# SDRAM.net
KiCad netlist of a schematic drawn in Altium Designer
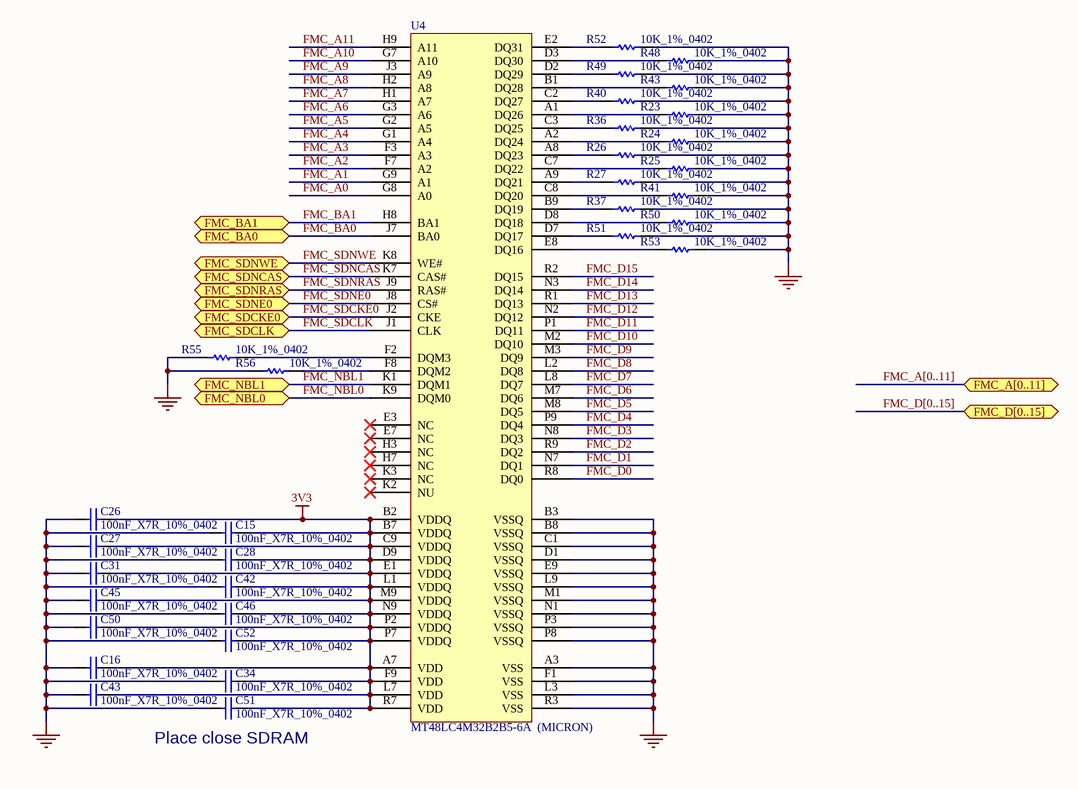
[diagram p0: SDRAM.SchDoc]

(export (version "E")
  (design (tool "Eeschema 10.0.6"))
  (components
    (comp (ref "C15")
      (value "100nF_X7R_10%_0402")
      (footprint "0402C")
      (description "Capacitor,100nF,16V,X7R,10%,0402,YAGEO")
      (libsource (lib "MCD_TOOLS") (part "Cap_100nF_X7R_10%_0402"))
    )
    (comp (ref "C16")
      (value "100nF_X7R_10%_0402")
      (footprint "0402C")
      (description "Capacitor,100nF,16V,X7R,10%,0402,YAGEO")
      (libsource (lib "MCD_TOOLS") (part "Cap_100nF_X7R_10%_0402"))
    )
    (comp (ref "C26")
      (value "100nF_X7R_10%_0402")
      (footprint "0402C")
      (description "Capacitor,100nF,16V,X7R,10%,0402,YAGEO")
      (libsource (lib "MCD_TOOLS") (part "Cap_100nF_X7R_10%_0402"))
    )
    (comp (ref "C27")
      (value "100nF_X7R_10%_0402")
      (footprint "0402C")
      (description "Capacitor,100nF,16V,X7R,10%,0402,YAGEO")
      (libsource (lib "MCD_TOOLS") (part "Cap_100nF_X7R_10%_0402"))
    )
    (comp (ref "C28")
      (value "100nF_X7R_10%_0402")
      (footprint "0402C")
      (description "Capacitor,100nF,16V,X7R,10%,0402,YAGEO")
      (libsource (lib "MCD_TOOLS") (part "Cap_100nF_X7R_10%_0402"))
    )
    (comp (ref "C31")
      (value "100nF_X7R_10%_0402")
      (footprint "0402C")
      (description "Capacitor,100nF,16V,X7R,10%,0402,YAGEO")
      (libsource (lib "MCD_TOOLS") (part "Cap_100nF_X7R_10%_0402"))
    )
    (comp (ref "C34")
      (value "100nF_X7R_10%_0402")
      (footprint "0402C")
      (description "Capacitor,100nF,16V,X7R,10%,0402,YAGEO")
      (libsource (lib "MCD_TOOLS") (part "Cap_100nF_X7R_10%_0402"))
    )
    (comp (ref "C42")
      (value "100nF_X7R_10%_0402")
      (footprint "0402C")
      (description "Capacitor,100nF,16V,X7R,10%,0402,YAGEO")
      (libsource (lib "MCD_TOOLS") (part "Cap_100nF_X7R_10%_0402"))
    )
    (comp (ref "C43")
      (value "100nF_X7R_10%_0402")
      (footprint "0402C")
      (description "Capacitor,100nF,16V,X7R,10%,0402,YAGEO")
      (libsource (lib "MCD_TOOLS") (part "Cap_100nF_X7R_10%_0402"))
    )
    (comp (ref "C45")
      (value "100nF_X7R_10%_0402")
      (footprint "0402C")
      (description "Capacitor,100nF,16V,X7R,10%,0402,YAGEO")
      (libsource (lib "MCD_TOOLS") (part "Cap_100nF_X7R_10%_0402"))
    )
    (comp (ref "C46")
      (value "100nF_X7R_10%_0402")
      (footprint "0402C")
      (description "Capacitor,100nF,16V,X7R,10%,0402,YAGEO")
      (libsource (lib "MCD_TOOLS") (part "Cap_100nF_X7R_10%_0402"))
    )
    (comp (ref "C50")
      (value "100nF_X7R_10%_0402")
      (footprint "0402C")
      (description "Capacitor,100nF,16V,X7R,10%,0402,YAGEO")
      (libsource (lib "MCD_TOOLS") (part "Cap_100nF_X7R_10%_0402"))
    )
    (comp (ref "C51")
      (value "100nF_X7R_10%_0402")
      (footprint "0402C")
      (description "Capacitor,100nF,16V,X7R,10%,0402,YAGEO")
      (libsource (lib "MCD_TOOLS") (part "Cap_100nF_X7R_10%_0402"))
    )
    (comp (ref "C52")
      (value "100nF_X7R_10%_0402")
      (footprint "0402C")
      (description "Capacitor,100nF,16V,X7R,10%,0402,YAGEO")
      (libsource (lib "MCD_TOOLS") (part "Cap_100nF_X7R_10%_0402"))
    )
    (comp (ref "R23")
      (value "10K_1%_0402")
      (footprint "0402R")
      (description "Resistor,10K,0402,1%,YAGEO")
      (libsource (lib "MCD_TOOLS") (part "Res_10K_1%_0402"))
    )
    (comp (ref "R24")
      (value "10K_1%_0402")
      (footprint "0402R")
      (description "Resistor,10K,0402,1%,YAGEO")
      (libsource (lib "MCD_TOOLS") (part "Res_10K_1%_0402"))
    )
    (comp (ref "R25")
      (value "10K_1%_0402")
      (footprint "0402R")
      (description "Resistor,10K,0402,1%,YAGEO")
      (libsource (lib "MCD_TOOLS") (part "Res_10K_1%_0402"))
    )
    (comp (ref "R26")
      (value "10K_1%_0402")
      (footprint "0402R")
      (description "Resistor,10K,0402,1%,YAGEO")
      (libsource (lib "MCD_TOOLS") (part "Res_10K_1%_0402"))
    )
    (comp (ref "R27")
      (value "10K_1%_0402")
      (footprint "0402R")
      (description "Resistor,10K,0402,1%,YAGEO")
      (libsource (lib "MCD_TOOLS") (part "Res_10K_1%_0402"))
    )
    (comp (ref "R36")
      (value "10K_1%_0402")
      (footprint "0402R")
      (description "Resistor,10K,0402,1%,YAGEO")
      (libsource (lib "MCD_TOOLS") (part "Res_10K_1%_0402"))
    )
    (comp (ref "R37")
      (value "10K_1%_0402")
      (footprint "0402R")
      (description "Resistor,10K,0402,1%,YAGEO")
      (libsource (lib "MCD_TOOLS") (part "Res_10K_1%_0402"))
    )
    (comp (ref "R40")
      (value "10K_1%_0402")
      (footprint "0402R")
      (description "Resistor,10K,0402,1%,YAGEO")
      (libsource (lib "MCD_TOOLS") (part "Res_10K_1%_0402"))
    )
    (comp (ref "R41")
      (value "10K_1%_0402")
      (footprint "0402R")
      (description "Resistor,10K,0402,1%,YAGEO")
      (libsource (lib "MCD_TOOLS") (part "Res_10K_1%_0402"))
    )
    (comp (ref "R43")
      (value "10K_1%_0402")
      (footprint "0402R")
      (description "Resistor,10K,0402,1%,YAGEO")
      (libsource (lib "MCD_TOOLS") (part "Res_10K_1%_0402"))
    )
    (comp (ref "R48")
      (value "10K_1%_0402")
      (footprint "0402R")
      (description "Resistor,10K,0402,1%,YAGEO")
      (libsource (lib "MCD_TOOLS") (part "Res_10K_1%_0402"))
    )
    (comp (ref "R49")
      (value "10K_1%_0402")
      (footprint "0402R")
      (description "Resistor,10K,0402,1%,YAGEO")
      (libsource (lib "MCD_TOOLS") (part "Res_10K_1%_0402"))
    )
    (comp (ref "R50")
      (value "10K_1%_0402")
      (footprint "0402R")
      (description "Resistor,10K,0402,1%,YAGEO")
      (libsource (lib "MCD_TOOLS") (part "Res_10K_1%_0402"))
    )
    (comp (ref "R51")
      (value "10K_1%_0402")
      (footprint "0402R")
      (description "Resistor,10K,0402,1%,YAGEO")
      (libsource (lib "MCD_TOOLS") (part "Res_10K_1%_0402"))
    )
    (comp (ref "R52")
      (value "10K_1%_0402")
      (footprint "0402R")
      (description "Resistor,10K,0402,1%,YAGEO")
      (libsource (lib "MCD_TOOLS") (part "Res_10K_1%_0402"))
    )
    (comp (ref "R53")
      (value "10K_1%_0402")
      (footprint "0402R")
      (description "Resistor,10K,0402,1%,YAGEO")
      (libsource (lib "MCD_TOOLS") (part "Res_10K_1%_0402"))
    )
    (comp (ref "R55")
      (value "10K_1%_0402")
      (footprint "0402R")
      (description "Resistor,10K,0402,1%,YAGEO")
      (libsource (lib "MCD_TOOLS") (part "Res_10K_1%_0402"))
    )
    (comp (ref "R56")
      (value "10K_1%_0402")
      (footprint "0402R")
      (description "Resistor,10K,0402,1%,YAGEO")
      (libsource (lib "MCD_TOOLS") (part "Res_10K_1%_0402"))
    )
    (comp (ref "U4")
      (value "MT48LC4M32B2B5-6A  (MICRON)")
      (footprint "FBGA90_0R8_8X13")
      (description "SDRAM 128MBIT (4M x 32) 166MHZ 90-VFBGA (8x13)")
      (libsource (lib "MCD_TOOLS") (part "MT48LC4M32B2B5-6A"))
    )
  )
  (nets
    (net (code "1") (name "/FMC_A0") (class "Default")
      (node (ref "U4") (pin "G8") (pinfunction "A0_G8") (pintype "passive"))
    )
    (net (code "2") (name "/FMC_A1") (class "Default")
      (node (ref "U4") (pin "G9") (pinfunction "A1_G9") (pintype "passive"))
    )
    (net (code "3") (name "/FMC_A2") (class "Default")
      (node (ref "U4") (pin "F7") (pinfunction "A2_F7") (pintype "passive"))
    )
    (net (code "4") (name "/FMC_A3") (class "Default")
      (node (ref "U4") (pin "F3") (pinfunction "A3_F3") (pintype "passive"))
    )
    (net (code "5") (name "/FMC_A4") (class "Default")
      (node (ref "U4") (pin "G1") (pinfunction "A4_G1") (pintype "passive"))
    )
    (net (code "6") (name "/FMC_A5") (class "Default")
      (node (ref "U4") (pin "G2") (pinfunction "A5_G2") (pintype "passive"))
    )
    (net (code "7") (name "/FMC_A6") (class "Default")
      (node (ref "U4") (pin "G3") (pinfunction "A6_G3") (pintype "passive"))
    )
    (net (code "8") (name "/FMC_A7") (class "Default")
      (node (ref "U4") (pin "H1") (pinfunction "A7_H1") (pintype "passive"))
    )
    (net (code "9") (name "/FMC_A8") (class "Default")
      (node (ref "U4") (pin "H2") (pinfunction "A8_H2") (pintype "passive"))
    )
    (net (code "10") (name "/FMC_A9") (class "Default")
      (node (ref "U4") (pin "J3") (pinfunction "A9_J3") (pintype "passive"))
    )
    (net (code "11") (name "/FMC_A10") (class "Default")
      (node (ref "U4") (pin "G7") (pinfunction "A10_G7") (pintype "passive"))
    )
    (net (code "12") (name "/FMC_A11") (class "Default")
      (node (ref "U4") (pin "H9") (pinfunction "A11_H9") (pintype "passive"))
    )
    (net (code "14") (name "/FMC_BA0") (class "Default")
      (node (ref "U4") (pin "J7") (pinfunction "BA0_J7") (pintype "passive"))
    )
    (net (code "15") (name "/FMC_BA1") (class "Default")
      (node (ref "U4") (pin "H8") (pinfunction "BA1_H8") (pintype "passive"))
    )
    (net (code "16") (name "/FMC_D0") (class "Default")
      (node (ref "U4") (pin "R8") (pinfunction "DQ0_R8") (pintype "passive"))
    )
    (net (code "17") (name "/FMC_D1") (class "Default")
      (node (ref "U4") (pin "N7") (pinfunction "DQ1_N7") (pintype "passive"))
    )
    (net (code "18") (name "/FMC_D2") (class "Default")
      (node (ref "U4") (pin "R9") (pinfunction "DQ2_R9") (pintype "passive"))
    )
    (net (code "19") (name "/FMC_D3") (class "Default")
      (node (ref "U4") (pin "N8") (pinfunction "DQ3_N8") (pintype "passive"))
    )
    (net (code "20") (name "/FMC_D4") (class "Default")
      (node (ref "U4") (pin "P9") (pinfunction "DQ4_P9") (pintype "passive"))
    )
    (net (code "21") (name "/FMC_D5") (class "Default")
      (node (ref "U4") (pin "M8") (pinfunction "DQ5_M8") (pintype "passive"))
    )
    (net (code "22") (name "/FMC_D6") (class "Default")
      (node (ref "U4") (pin "M7") (pinfunction "DQ6_M7") (pintype "passive"))
    )
    (net (code "23") (name "/FMC_D7") (class "Default")
      (node (ref "U4") (pin "L8") (pinfunction "DQ7_L8") (pintype "passive"))
    )
    (net (code "24") (name "/FMC_D8") (class "Default")
      (node (ref "U4") (pin "L2") (pinfunction "DQ8_L2") (pintype "passive"))
    )
    (net (code "25") (name "/FMC_D9") (class "Default")
      (node (ref "U4") (pin "M3") (pinfunction "DQ9_M3") (pintype "passive"))
    )
    (net (code "26") (name "/FMC_D10") (class "Default")
      (node (ref "U4") (pin "M2") (pinfunction "DQ10_M2") (pintype "passive"))
    )
    (net (code "27") (name "/FMC_D11") (class "Default")
      (node (ref "U4") (pin "P1") (pinfunction "DQ11_P1") (pintype "passive"))
    )
    (net (code "28") (name "/FMC_D12") (class "Default")
      (node (ref "U4") (pin "N2") (pinfunction "DQ12_N2") (pintype "passive"))
    )
    (net (code "29") (name "/FMC_D13") (class "Default")
      (node (ref "U4") (pin "R1") (pinfunction "DQ13_R1") (pintype "passive"))
    )
    (net (code "30") (name "/FMC_D14") (class "Default")
      (node (ref "U4") (pin "N3") (pinfunction "DQ14_N3") (pintype "passive"))
    )
    (net (code "31") (name "/FMC_D15") (class "Default")
      (node (ref "U4") (pin "R2") (pinfunction "DQ15_R2") (pintype "passive"))
    )
    (net (code "33") (name "/FMC_NBL0") (class "Default")
      (node (ref "U4") (pin "K9") (pinfunction "DQM0_K9") (pintype "passive"))
    )
    (net (code "34") (name "/FMC_NBL1") (class "Default")
      (node (ref "U4") (pin "K1") (pinfunction "DQM1_K1") (pintype "passive"))
    )
    (net (code "35") (name "/FMC_SDCKE0") (class "Default")
      (node (ref "U4") (pin "J2") (pinfunction "CKE_J2") (pintype "passive"))
    )
    (net (code "36") (name "/FMC_SDCLK") (class "Default")
      (node (ref "U4") (pin "J1") (pinfunction "CLK_J1") (pintype "passive"))
    )
    (net (code "37") (name "/FMC_SDNCAS") (class "Default")
      (node (ref "U4") (pin "K7") (pinfunction "CAS#_K7") (pintype "passive"))
    )
    (net (code "38") (name "/FMC_SDNE0") (class "Default")
      (node (ref "U4") (pin "J8") (pinfunction "CS#_J8") (pintype "passive"))
    )
    (net (code "39") (name "/FMC_SDNRAS") (class "Default")
      (node (ref "U4") (pin "J9") (pinfunction "RAS#_J9") (pintype "passive"))
    )
    (net (code "40") (name "/FMC_SDNWE") (class "Default")
      (node (ref "U4") (pin "K8") (pinfunction "WE#_K8") (pintype "passive"))
    )
    (net (code "41") (name "3V3") (class "Default")
      (node (ref "C15") (pin "2") (pinfunction "2_2") (pintype "passive"))
      (node (ref "C16") (pin "2") (pinfunction "2_2") (pintype "passive"))
      (node (ref "C26") (pin "2") (pinfunction "2_2") (pintype "passive"))
      (node (ref "C27") (pin "2") (pinfunction "2_2") (pintype "passive"))
      (node (ref "C28") (pin "2") (pinfunction "2_2") (pintype "passive"))
      (node (ref "C31") (pin "2") (pinfunction "2_2") (pintype "passive"))
      (node (ref "C34") (pin "2") (pinfunction "2_2") (pintype "passive"))
      (node (ref "C42") (pin "2") (pinfunction "2_2") (pintype "passive"))
      (node (ref "C43") (pin "2") (pinfunction "2_2") (pintype "passive"))
      (node (ref "C45") (pin "2") (pinfunction "2_2") (pintype "passive"))
      (node (ref "C46") (pin "2") (pinfunction "2_2") (pintype "passive"))
      (node (ref "C50") (pin "2") (pinfunction "2_2") (pintype "passive"))
      (node (ref "C51") (pin "2") (pinfunction "2_2") (pintype "passive"))
      (node (ref "C52") (pin "2") (pinfunction "2_2") (pintype "passive"))
      (node (ref "U4") (pin "A7") (pinfunction "VDD_A7") (pintype "passive"))
      (node (ref "U4") (pin "B2") (pinfunction "VDDQ_B2") (pintype "passive"))
      (node (ref "U4") (pin "B7") (pinfunction "VDDQ_B7") (pintype "passive"))
      (node (ref "U4") (pin "C9") (pinfunction "VDDQ_C9") (pintype "passive"))
      (node (ref "U4") (pin "D9") (pinfunction "VDDQ_D9") (pintype "passive"))
      (node (ref "U4") (pin "E1") (pinfunction "VDDQ_E1") (pintype "passive"))
      (node (ref "U4") (pin "F9") (pinfunction "VDD_F9") (pintype "passive"))
      (node (ref "U4") (pin "L1") (pinfunction "VDDQ_L1") (pintype "passive"))
      (node (ref "U4") (pin "L7") (pinfunction "VDD_L7") (pintype "passive"))
      (node (ref "U4") (pin "M9") (pinfunction "VDDQ_M9") (pintype "passive"))
      (node (ref "U4") (pin "N9") (pinfunction "VDDQ_N9") (pintype "passive"))
      (node (ref "U4") (pin "P2") (pinfunction "VDDQ_P2") (pintype "passive"))
      (node (ref "U4") (pin "P7") (pinfunction "VDDQ_P7") (pintype "passive"))
      (node (ref "U4") (pin "R7") (pinfunction "VDD_R7") (pintype "passive"))
    )
    (net (code "42") (name "GND") (class "Default")
      (node (ref "C15") (pin "1") (pinfunction "1_1") (pintype "passive"))
      (node (ref "C16") (pin "1") (pinfunction "1_1") (pintype "passive"))
      (node (ref "C26") (pin "1") (pinfunction "1_1") (pintype "passive"))
      (node (ref "C27") (pin "1") (pinfunction "1_1") (pintype "passive"))
      (node (ref "C28") (pin "1") (pinfunction "1_1") (pintype "passive"))
      (node (ref "C31") (pin "1") (pinfunction "1_1") (pintype "passive"))
      (node (ref "C34") (pin "1") (pinfunction "1_1") (pintype "passive"))
      (node (ref "C42") (pin "1") (pinfunction "1_1") (pintype "passive"))
      (node (ref "C43") (pin "1") (pinfunction "1_1") (pintype "passive"))
      (node (ref "C45") (pin "1") (pinfunction "1_1") (pintype "passive"))
      (node (ref "C46") (pin "1") (pinfunction "1_1") (pintype "passive"))
      (node (ref "C50") (pin "1") (pinfunction "1_1") (pintype "passive"))
      (node (ref "C51") (pin "1") (pinfunction "1_1") (pintype "passive"))
      (node (ref "C52") (pin "1") (pinfunction "1_1") (pintype "passive"))
      (node (ref "R23") (pin "2") (pinfunction "2_2") (pintype "passive"))
      (node (ref "R24") (pin "2") (pinfunction "2_2") (pintype "passive"))
      (node (ref "R25") (pin "2") (pinfunction "2_2") (pintype "passive"))
      (node (ref "R26") (pin "2") (pinfunction "2_2") (pintype "passive"))
      (node (ref "R27") (pin "2") (pinfunction "2_2") (pintype "passive"))
      (node (ref "R36") (pin "2") (pinfunction "2_2") (pintype "passive"))
      (node (ref "R37") (pin "2") (pinfunction "2_2") (pintype "passive"))
      (node (ref "R40") (pin "2") (pinfunction "2_2") (pintype "passive"))
      (node (ref "R41") (pin "2") (pinfunction "2_2") (pintype "passive"))
      (node (ref "R43") (pin "2") (pinfunction "2_2") (pintype "passive"))
      (node (ref "R48") (pin "2") (pinfunction "2_2") (pintype "passive"))
      (node (ref "R49") (pin "2") (pinfunction "2_2") (pintype "passive"))
      (node (ref "R50") (pin "2") (pinfunction "2_2") (pintype "passive"))
      (node (ref "R51") (pin "2") (pinfunction "2_2") (pintype "passive"))
      (node (ref "R52") (pin "2") (pinfunction "2_2") (pintype "passive"))
      (node (ref "R53") (pin "2") (pinfunction "2_2") (pintype "passive"))
      (node (ref "R55") (pin "1") (pinfunction "1_1") (pintype "passive"))
      (node (ref "R56") (pin "1") (pinfunction "1_1") (pintype "passive"))
      (node (ref "U4") (pin "A3") (pinfunction "VSS_A3") (pintype "passive"))
      (node (ref "U4") (pin "B3") (pinfunction "VSSQ_B3") (pintype "passive"))
      (node (ref "U4") (pin "B8") (pinfunction "VSSQ_B8") (pintype "passive"))
      (node (ref "U4") (pin "C1") (pinfunction "VSSQ_C1") (pintype "passive"))
      (node (ref "U4") (pin "D1") (pinfunction "VSSQ_D1") (pintype "passive"))
      (node (ref "U4") (pin "E9") (pinfunction "VSSQ_E9") (pintype "passive"))
      (node (ref "U4") (pin "F1") (pinfunction "VSS_F1") (pintype "passive"))
      (node (ref "U4") (pin "L3") (pinfunction "VSS_L3") (pintype "passive"))
      (node (ref "U4") (pin "L9") (pinfunction "VSSQ_L9") (pintype "passive"))
      (node (ref "U4") (pin "M1") (pinfunction "VSSQ_M1") (pintype "passive"))
      (node (ref "U4") (pin "N1") (pinfunction "VSSQ_N1") (pintype "passive"))
      (node (ref "U4") (pin "P3") (pinfunction "VSSQ_P3") (pintype "passive"))
      (node (ref "U4") (pin "P8") (pinfunction "VSSQ_P8") (pintype "passive"))
      (node (ref "U4") (pin "R3") (pinfunction "VSS_R3") (pintype "passive"))
    )
    (net (code "43") (name "Net-(U4-DQ16)") (class "Default")
      (node (ref "R53") (pin "1") (pinfunction "1_1") (pintype "passive"))
      (node (ref "U4") (pin "E8") (pinfunction "DQ16_E8") (pintype "passive"))
    )
    (net (code "44") (name "Net-(U4-DQ17)") (class "Default")
      (node (ref "R51") (pin "1") (pinfunction "1_1") (pintype "passive"))
      (node (ref "U4") (pin "D7") (pinfunction "DQ17_D7") (pintype "passive"))
    )
    (net (code "45") (name "Net-(U4-DQ18)") (class "Default")
      (node (ref "R50") (pin "1") (pinfunction "1_1") (pintype "passive"))
      (node (ref "U4") (pin "D8") (pinfunction "DQ18_D8") (pintype "passive"))
    )
    (net (code "46") (name "Net-(U4-DQ19)") (class "Default")
      (node (ref "R37") (pin "1") (pinfunction "1_1") (pintype "passive"))
      (node (ref "U4") (pin "B9") (pinfunction "DQ19_B9") (pintype "passive"))
    )
    (net (code "47") (name "Net-(U4-DQ20)") (class "Default")
      (node (ref "R41") (pin "1") (pinfunction "1_1") (pintype "passive"))
      (node (ref "U4") (pin "C8") (pinfunction "DQ20_C8") (pintype "passive"))
    )
    (net (code "48") (name "Net-(U4-DQ21)") (class "Default")
      (node (ref "R27") (pin "1") (pinfunction "1_1") (pintype "passive"))
      (node (ref "U4") (pin "A9") (pinfunction "DQ21_A9") (pintype "passive"))
    )
    (net (code "49") (name "Net-(U4-DQ22)") (class "Default")
      (node (ref "R25") (pin "1") (pinfunction "1_1") (pintype "passive"))
      (node (ref "U4") (pin "C7") (pinfunction "DQ22_C7") (pintype "passive"))
    )
    (net (code "50") (name "Net-(U4-DQ23)") (class "Default")
      (node (ref "R26") (pin "1") (pinfunction "1_1") (pintype "passive"))
      (node (ref "U4") (pin "A8") (pinfunction "DQ23_A8") (pintype "passive"))
    )
    (net (code "51") (name "Net-(U4-DQ24)") (class "Default")
      (node (ref "R24") (pin "1") (pinfunction "1_1") (pintype "passive"))
      (node (ref "U4") (pin "A2") (pinfunction "DQ24_A2") (pintype "passive"))
    )
    (net (code "52") (name "Net-(U4-DQ25)") (class "Default")
      (node (ref "R36") (pin "1") (pinfunction "1_1") (pintype "passive"))
      (node (ref "U4") (pin "C3") (pinfunction "DQ25_C3") (pintype "passive"))
    )
    (net (code "53") (name "Net-(U4-DQ26)") (class "Default")
      (node (ref "R23") (pin "1") (pinfunction "1_1") (pintype "passive"))
      (node (ref "U4") (pin "A1") (pinfunction "DQ26_A1") (pintype "passive"))
    )
    (net (code "54") (name "Net-(U4-DQ27)") (class "Default")
      (node (ref "R40") (pin "1") (pinfunction "1_1") (pintype "passive"))
      (node (ref "U4") (pin "C2") (pinfunction "DQ27_C2") (pintype "passive"))
    )
    (net (code "55") (name "Net-(U4-DQ28)") (class "Default")
      (node (ref "R43") (pin "1") (pinfunction "1_1") (pintype "passive"))
      (node (ref "U4") (pin "B1") (pinfunction "DQ28_B1") (pintype "passive"))
    )
    (net (code "56") (name "Net-(U4-DQ29)") (class "Default")
      (node (ref "R49") (pin "1") (pinfunction "1_1") (pintype "passive"))
      (node (ref "U4") (pin "D2") (pinfunction "DQ29_D2") (pintype "passive"))
    )
    (net (code "57") (name "Net-(U4-DQ30)") (class "Default")
      (node (ref "R48") (pin "1") (pinfunction "1_1") (pintype "passive"))
      (node (ref "U4") (pin "D3") (pinfunction "DQ30_D3") (pintype "passive"))
    )
    (net (code "58") (name "Net-(U4-DQ31)") (class "Default")
      (node (ref "R52") (pin "1") (pinfunction "1_1") (pintype "passive"))
      (node (ref "U4") (pin "E2") (pinfunction "DQ31_E2") (pintype "passive"))
    )
    (net (code "59") (name "Net-(U4-DQM2)") (class "Default")
      (node (ref "R56") (pin "2") (pinfunction "2_2") (pintype "passive"))
      (node (ref "U4") (pin "F8") (pinfunction "DQM2_F8") (pintype "passive"))
    )
    (net (code "60") (name "Net-(U4-DQM3)") (class "Default")
      (node (ref "R55") (pin "2") (pinfunction "2_2") (pintype "passive"))
      (node (ref "U4") (pin "F2") (pinfunction "DQM3_F2") (pintype "passive"))
    )
    (net (code "61") (name "unconnected-(U4-NC-PadE3)") (class "Default")
      (node (ref "U4") (pin "E3") (pinfunction "NC_E3") (pintype "passive+no_connect"))
    )
    (net (code "62") (name "unconnected-(U4-NC-PadE7)") (class "Default")
      (node (ref "U4") (pin "E7") (pinfunction "NC_E7") (pintype "passive+no_connect"))
    )
    (net (code "63") (name "unconnected-(U4-NC-PadH3)") (class "Default")
      (node (ref "U4") (pin "H3") (pinfunction "NC_H3") (pintype "passive+no_connect"))
    )
    (net (code "64") (name "unconnected-(U4-NC-PadH7)") (class "Default")
      (node (ref "U4") (pin "H7") (pinfunction "NC_H7") (pintype "passive+no_connect"))
    )
    (net (code "65") (name "unconnected-(U4-NC-PadK3)") (class "Default")
      (node (ref "U4") (pin "K3") (pinfunction "NC_K3") (pintype "passive+no_connect"))
    )
    (net (code "66") (name "unconnected-(U4-NU-PadK2)") (class "Default")
      (node (ref "U4") (pin "K2") (pinfunction "NU_K2") (pintype "passive+no_connect"))
    )
  )
)
